# FPGA_DDR3_IO.net
KiCad netlist of a schematic drawn in Altium Designer
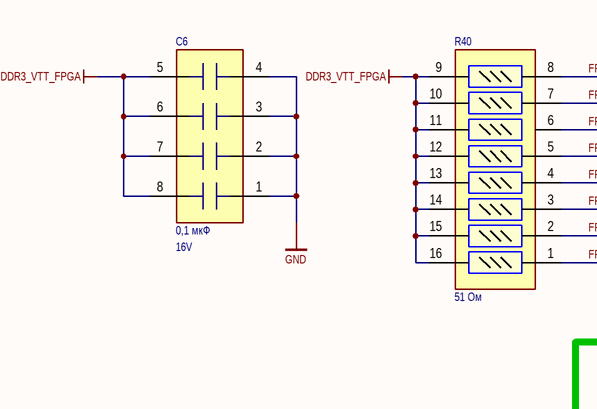
[diagram p0: FPGA_DDR3&IO.SchDoc, top left]
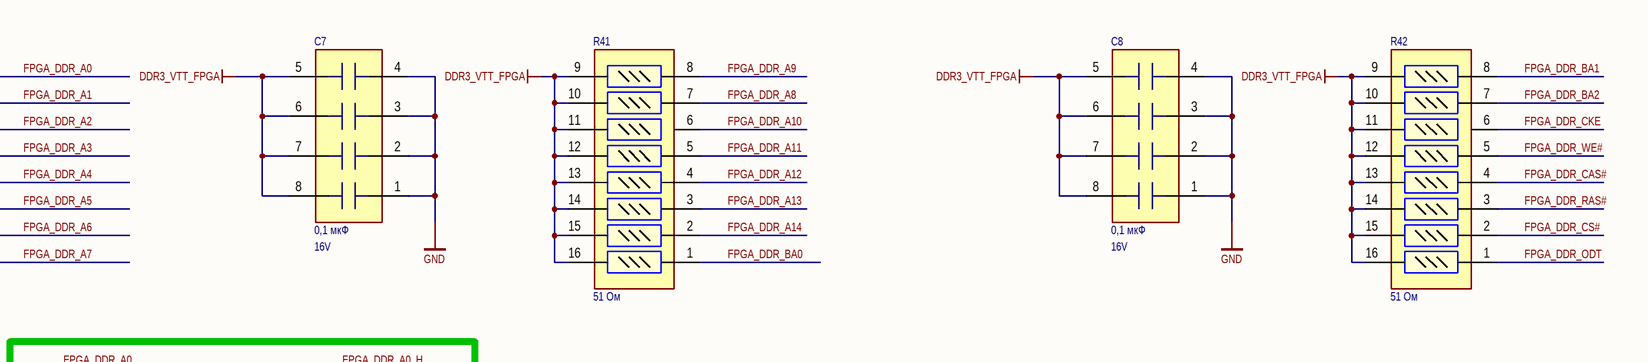
[diagram p1: FPGA_DDR3&IO.SchDoc, top right]
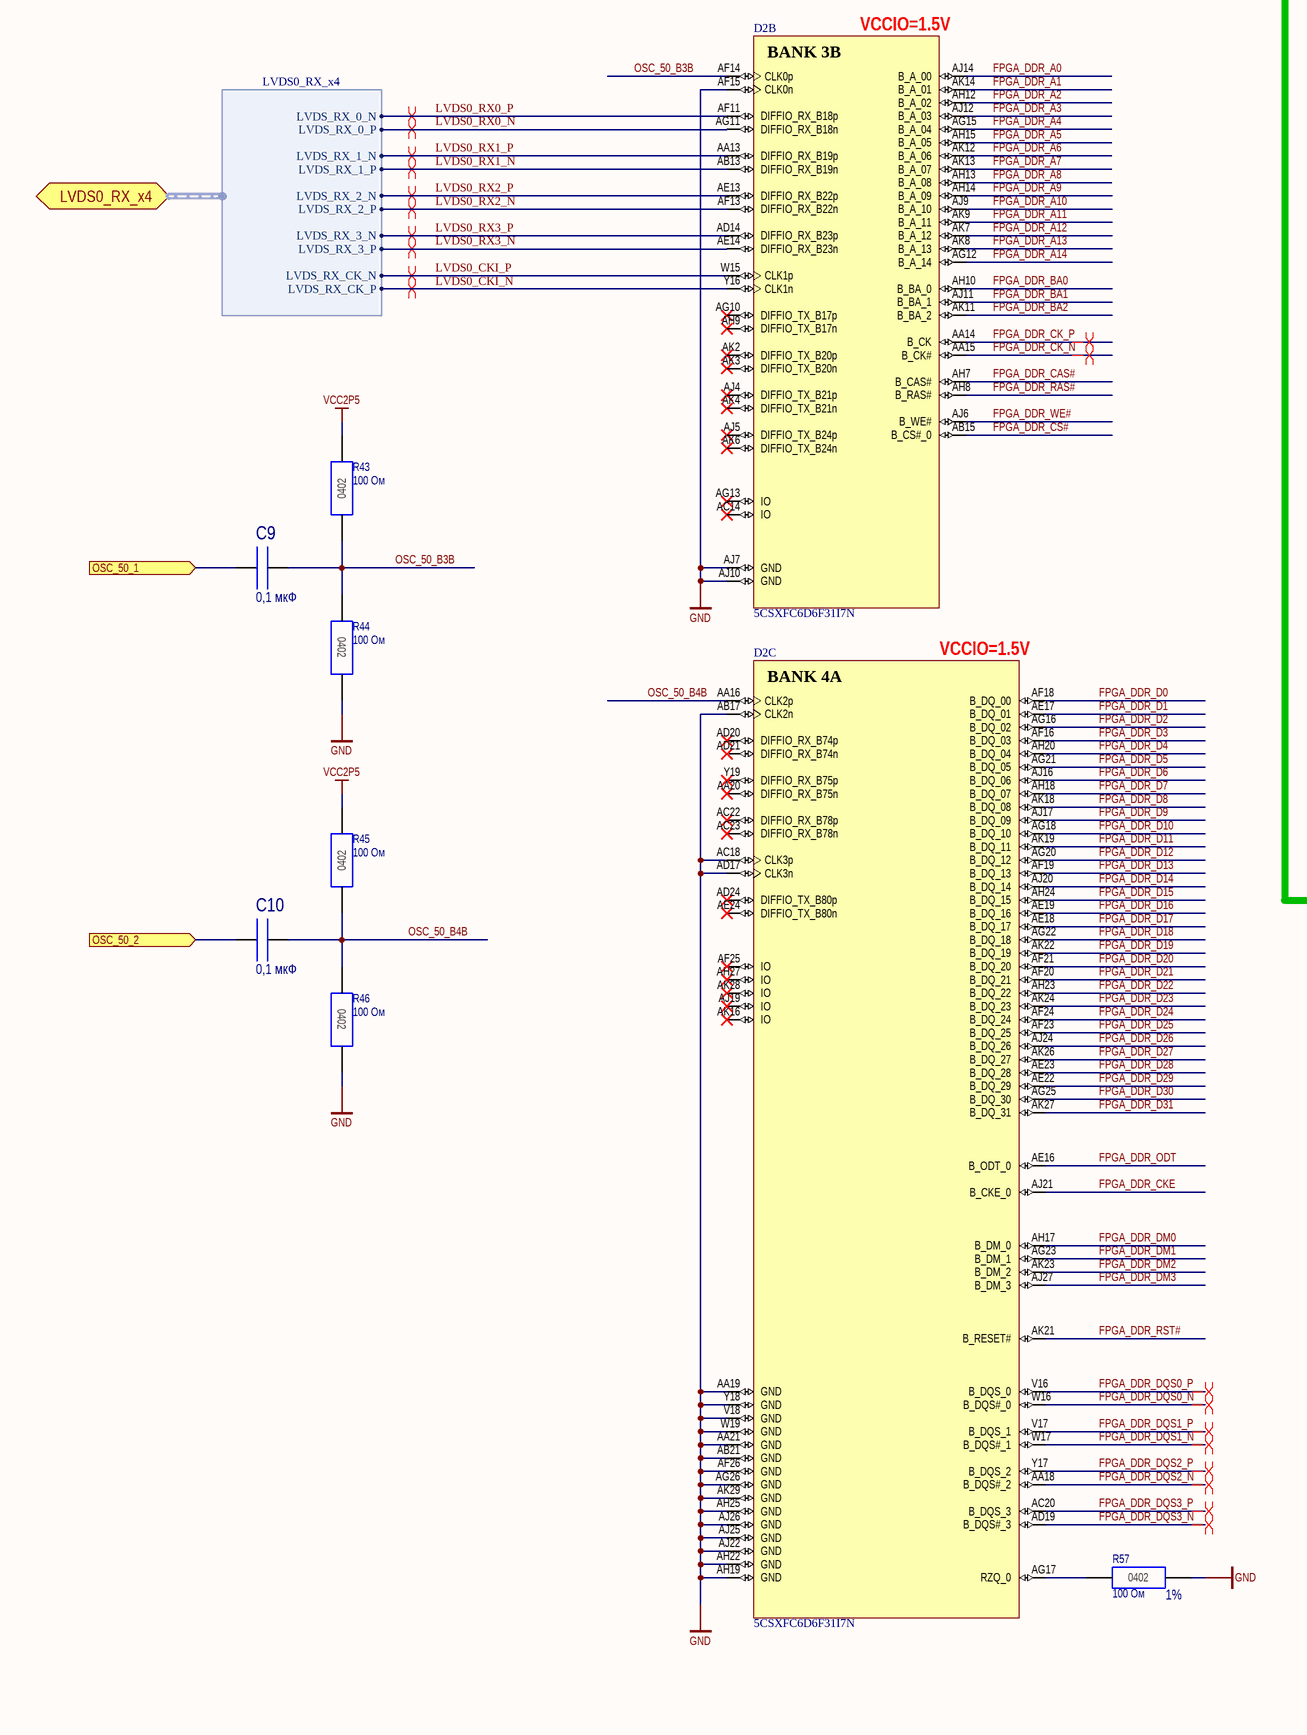
[diagram p2: FPGA_DDR3&IO.SchDoc, bottom left]
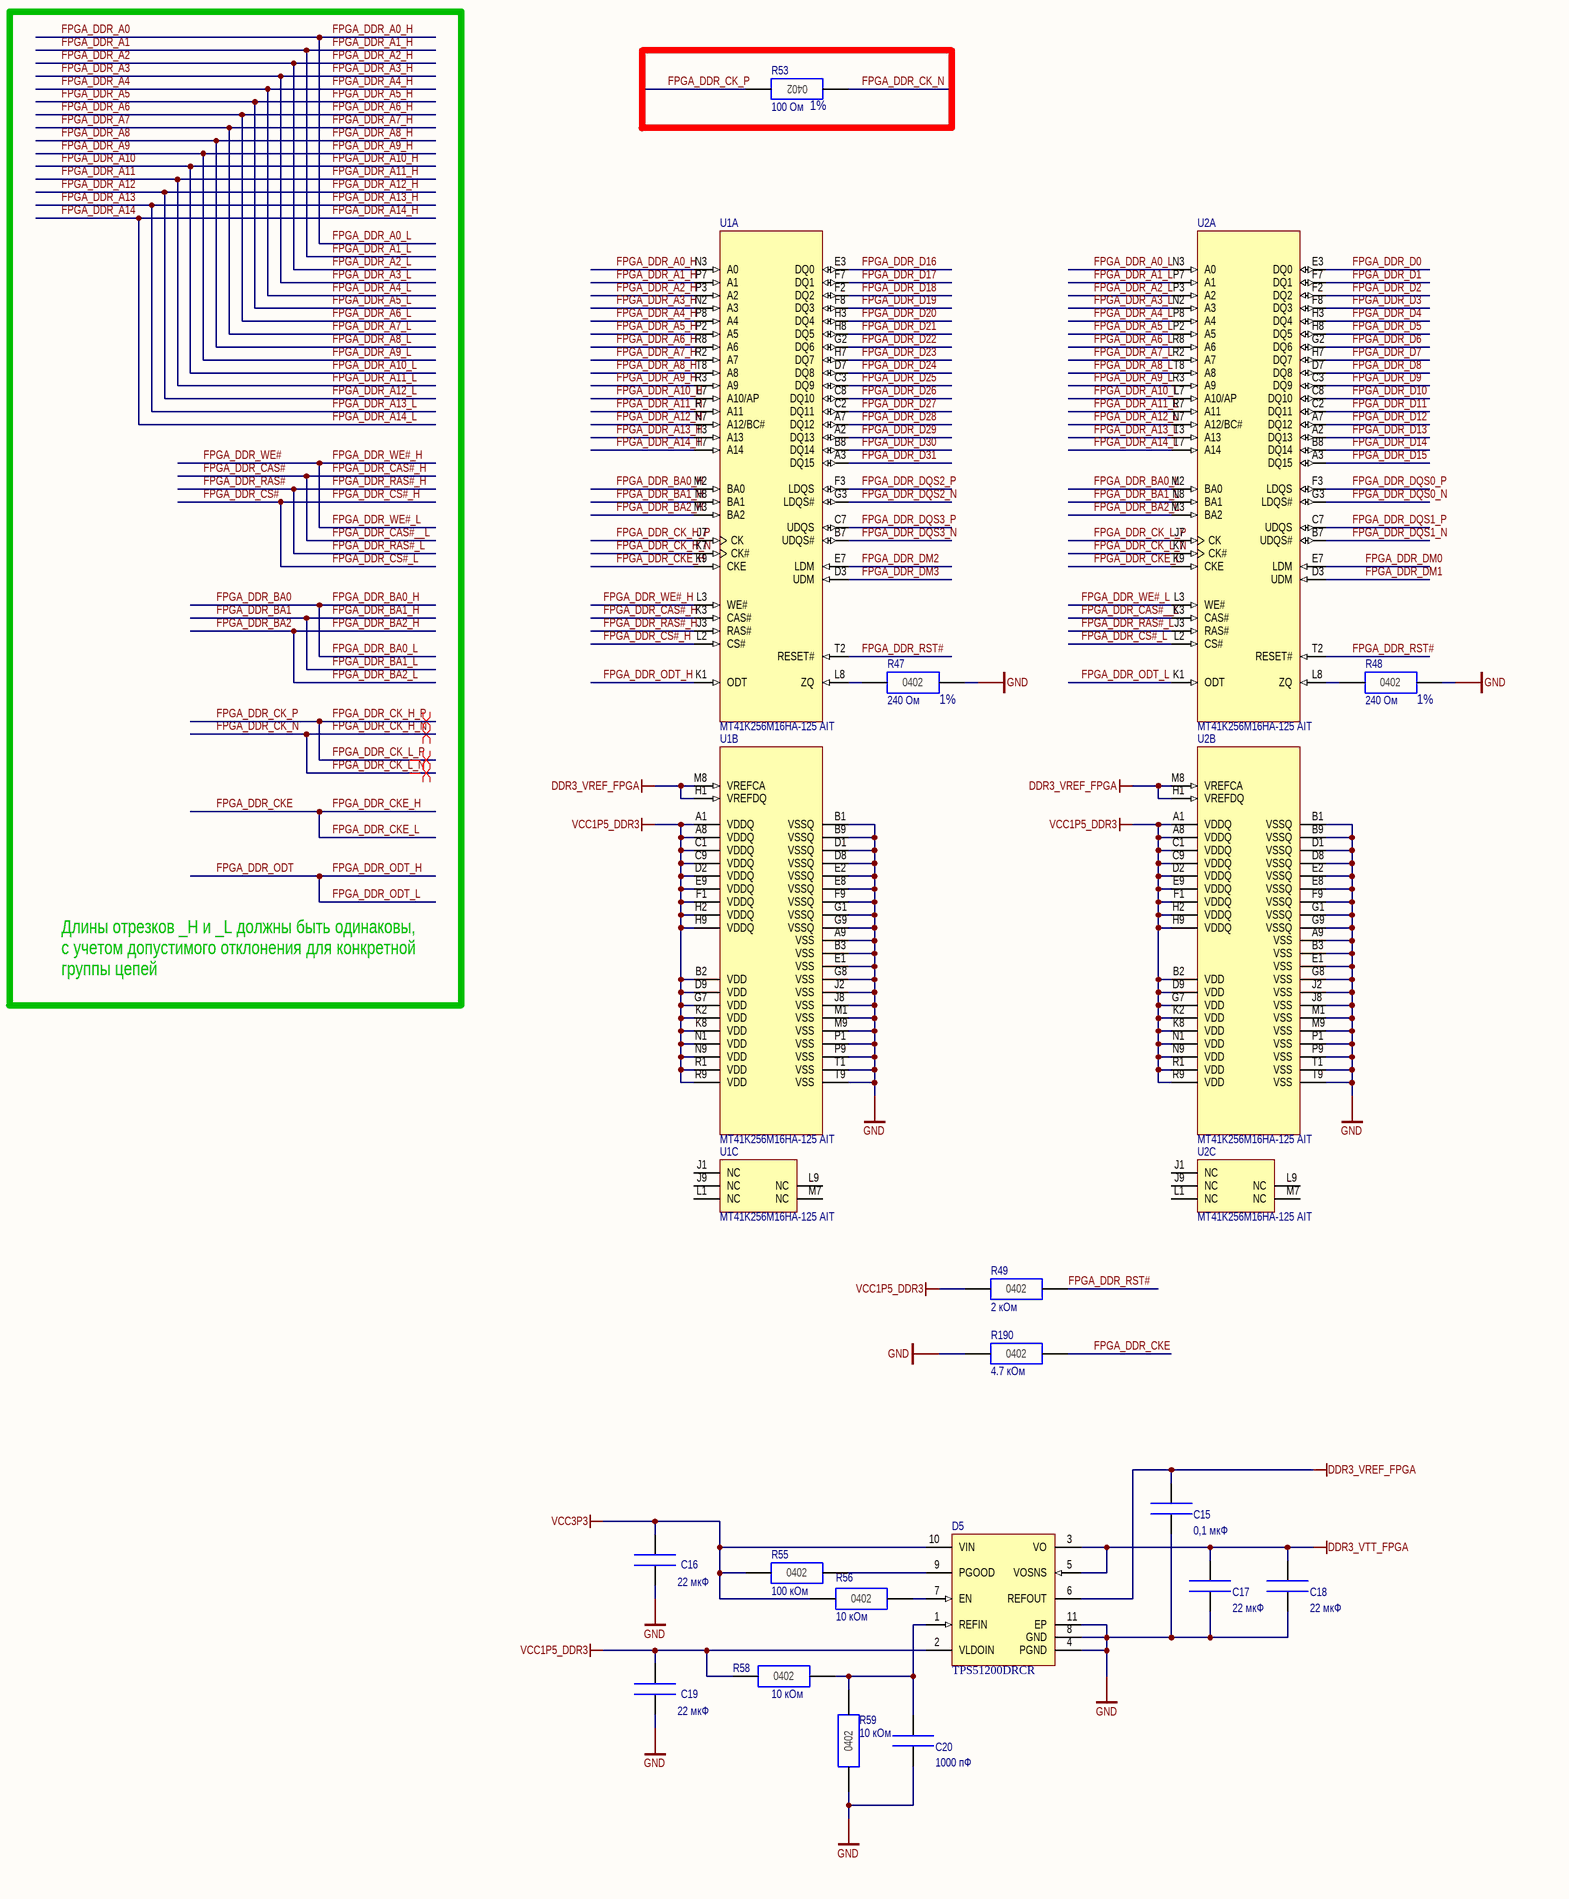
[diagram p3: FPGA_DDR3&IO.SchDoc, bottom right]

(export (version "E")
  (design (tool "Eeschema 10.0.6"))
  (components
    (comp (ref "C6")
      (value "0,1 мкФ")
      (footprint "CAF-80P319X159-8N")
      (description "Чип конденсатор керамический")
      (fields (field (name "V") "16V") (field (name "Comment") "W3A4YC104KAT2A"))
      (libsource (lib "SD_IC") (part "W3A4YC104KAT2A"))
    )
    (comp (ref "C7")
      (value "0,1 мкФ")
      (footprint "CAF-80P319X159-8N")
      (description "Чип конденсатор керамический")
      (fields (field (name "V") "16V") (field (name "Comment") "W3A4YC104KAT2A"))
      (libsource (lib "SD_IC") (part "W3A4YC104KAT2A"))
    )
    (comp (ref "C8")
      (value "0,1 мкФ")
      (footprint "CAF-80P319X159-8N")
      (description "Чип конденсатор керамический")
      (fields (field (name "V") "16V") (field (name "Comment") "W3A4YC104KAT2A"))
      (libsource (lib "SD_IC") (part "W3A4YC104KAT2A"))
    )
    (comp (ref "C9")
      (value "0,1 мкФ")
      (footprint "CC0402(1005)")
      (description "Чип конденсатор керамический")
      (fields (field (name "Comment") "CC0402-X7R-0,1 мкФ-20%-10В"))
      (libsource (lib "Чип конденсаторы") (part "CC0402-X7R-#-20%-10В"))
    )
    (comp (ref "C10")
      (value "0,1 мкФ")
      (footprint "CC0402(1005)")
      (description "Чип конденсатор керамический")
      (fields (field (name "Comment") "CC0402-X7R-0,1 мкФ-20%-10В"))
      (libsource (lib "Чип конденсаторы") (part "CC0402-X7R-#-20%-10В"))
    )
    (comp (ref "C15")
      (value "0,1 мкФ")
      (footprint "CC0402(1005)")
      (description "Чип конденсатор керамический")
      (fields (field (name "Comment") "CC0402-X7R-0,1 мкФ-20%-10В"))
      (libsource (lib "Чип конденсаторы") (part "CC0402-X7R-#-20%-10В"))
    )
    (comp (ref "C16")
      (value "22 мкФ")
      (footprint "CC0402(1005)")
      (description "Чип конденсатор керамический")
      (fields (field (name "Comment") "CC0402-X5R-22 мкФ-20%-6.3В"))
      (libsource (lib "Чип конденсаторы") (part "CC0402-X7R-#-20%-10В"))
    )
    (comp (ref "C17")
      (value "22 мкФ")
      (footprint "CC0402(1005)")
      (description "Чип конденсатор керамический")
      (fields (field (name "Comment") "CC0402-X5R-22 мкФ-20%-6.3В"))
      (libsource (lib "Чип конденсаторы") (part "CC0402-X7R-#-20%-10В"))
    )
    (comp (ref "C18")
      (value "22 мкФ")
      (footprint "CC0402(1005)")
      (description "Чип конденсатор керамический")
      (fields (field (name "Comment") "CC0402-X5R-22 мкФ-20%-6.3В"))
      (libsource (lib "Чип конденсаторы") (part "CC0402-X7R-#-20%-10В"))
    )
    (comp (ref "C19")
      (value "22 мкФ")
      (footprint "CC0402(1005)")
      (description "Чип конденсатор керамический")
      (fields (field (name "Comment") "CC0402-X5R-22 мкФ-20%-6.3В"))
      (libsource (lib "Чип конденсаторы") (part "CC0402-X7R-#-20%-10В"))
    )
    (comp (ref "C20")
      (value "1000 пФ")
      (footprint "CC0402(1005)")
      (description "Чип конденсатор керамический")
      (fields (field (name "Comment") "CC0402-NP01000 пФ-1%-50В"))
      (libsource (lib "Чип конденсаторы") (part "CC0402-X7R-#-20%-10В"))
    )
    (comp (ref "D2")
      (value "5CSXFC6D6F31I7N")
      (footprint "ALTR-FBGA896_A-200")
      (fields (field (name "MANUFACTURER") "Altera"))
      (libsource (lib "Altera Cyclone V_sd") (part "5CSXFC6D6F31I7N"))
    )
    (comp (ref "D5")
      (value "TPS51200DRCR")
      (footprint "TI-DRC10-2400X1650TP_V")
      (fields (field (name "MANUFACTURER") "Texas Instruments"))
      (libsource (lib "SD_IC") (part "TPS51200DRCR"))
    )
    (comp (ref "R40")
      (value "51 Ом")
      (footprint "CAT16-J8")
      (description "Набор чип резисторов")
      (fields (field (name "Comment") "YC248-JR-07-51 Ом"))
      (libsource (lib "SD_IC") (part "YC248-JR-07-#"))
    )
    (comp (ref "R41")
      (value "51 Ом")
      (footprint "CAT16-J8")
      (description "Набор чип резисторов")
      (fields (field (name "Comment") "YC248-JR-07-51 Ом"))
      (libsource (lib "SD_IC") (part "YC248-JR-07-#"))
    )
    (comp (ref "R42")
      (value "51 Ом")
      (footprint "CAT16-J8")
      (description "Набор чип резисторов")
      (fields (field (name "Comment") "YC248-JR-07-51 Ом"))
      (libsource (lib "SD_IC") (part "YC248-JR-07-#"))
    )
    (comp (ref "R43")
      (value "100 Ом")
      (footprint "CR0402(1005)")
      (description "Чип резистор")
      (fields (field (name "TOLERANCE") "5%") (field (name "Comment") "CR0402-100 Ом-±5%"))
      (libsource (lib "") (part "CR0402-#-±5%_3"))
    )
    (comp (ref "R44")
      (value "100 Ом")
      (footprint "CR0402(1005)")
      (description "Чип резистор")
      (fields (field (name "TOLERANCE") "5%") (field (name "Comment") "CR0402-100 Ом-±5%"))
      (libsource (lib "") (part "CR0402-#-±5%_1"))
    )
    (comp (ref "R45")
      (value "100 Ом")
      (footprint "CR0402(1005)")
      (description "Чип резистор")
      (fields (field (name "TOLERANCE") "5%") (field (name "Comment") "CR0402-100 Ом-±5%"))
      (libsource (lib "") (part "CR0402-#-±5%_3"))
    )
    (comp (ref "R46")
      (value "100 Ом")
      (footprint "CR0402(1005)")
      (description "Чип резистор")
      (fields (field (name "TOLERANCE") "5%") (field (name "Comment") "CR0402-100 Ом-±5%"))
      (libsource (lib "") (part "CR0402-#-±5%_1"))
    )
    (comp (ref "R47")
      (value "240 Ом")
      (footprint "CR0402(1005)")
      (description "Чип резистор")
      (fields (field (name "TOLERANCE") "1%") (field (name "Comment") "CR0402-240 Ом-±TOLERANCE"))
      (libsource (lib "Резисторы") (part "CR0402-#-±5%"))
    )
    (comp (ref "R48")
      (value "240 Ом")
      (footprint "CR0402(1005)")
      (description "Чип резистор")
      (fields (field (name "TOLERANCE") "1%") (field (name "Comment") "CR0402-240 Ом-±TOLERANCE"))
      (libsource (lib "Резисторы") (part "CR0402-#-±5%"))
    )
    (comp (ref "R49")
      (value "2 кОм")
      (footprint "CR0402(1005)")
      (description "Чип резистор")
      (fields (field (name "TOLERANCE") "5%") (field (name "Comment") "CR0402-2 кОм-±5%"))
      (libsource (lib "Резисторы") (part "CR0402-#-±5%"))
    )
    (comp (ref "R53")
      (value "100 Ом")
      (footprint "CR0402(1005)")
      (description "Чип резистор")
      (fields (field (name "TOLERANCE") "1%") (field (name "Comment") "CR0402-100 Ом-±TOLERANCE"))
      (libsource (lib "") (part "CR0402-#-±5%_2"))
    )
    (comp (ref "R55")
      (value "100 кОм")
      (footprint "CR0402(1005)")
      (description "Чип резистор")
      (fields (field (name "TOLERANCE") "5%") (field (name "Comment") "CR0402-100 кОм-±5%"))
      (libsource (lib "Резисторы") (part "CR0402-#-±5%"))
    )
    (comp (ref "R56")
      (value "10 кОм")
      (footprint "CR0402(1005)")
      (description "Чип резистор")
      (fields (field (name "TOLERANCE") "5%") (field (name "Comment") "CR0402-10 кОм-±5%"))
      (libsource (lib "Резисторы") (part "CR0402-#-±5%"))
    )
    (comp (ref "R57")
      (value "100 Ом")
      (footprint "CR0402(1005)")
      (description "Чип резистор")
      (fields (field (name "TOLERANCE") "1%") (field (name "Comment") "CR0402-100 Ом-±TOLERANCE"))
      (libsource (lib "Резисторы") (part "CR0402-#-±5%"))
    )
    (comp (ref "R58")
      (value "10 кОм")
      (footprint "CR0402(1005)")
      (description "Чип резистор")
      (fields (field (name "TOLERANCE") "5%") (field (name "Comment") "CR0402-10 кОм-±5%"))
      (libsource (lib "Резисторы") (part "CR0402-#-±5%"))
    )
    (comp (ref "R59")
      (value "10 кОм")
      (footprint "CR0402(1005)")
      (description "Чип резистор")
      (fields (field (name "TOLERANCE") "5%") (field (name "Comment") "CR0402-10 кОм-±5%"))
      (libsource (lib "") (part "CR0402-#-±5%_3"))
    )
    (comp (ref "R190")
      (value "4.7 кОм")
      (footprint "CR0402(1005)")
      (description "Чип резистор")
      (fields (field (name "TOLERANCE") "5%") (field (name "Comment") "CR0402-4.7 кОм-±5%"))
      (libsource (lib "Резисторы") (part "CR0402-#-±5%"))
    )
    (comp (ref "U1")
      (value "MT41K256M16HA-125 AIT")
      (footprint "MICT-HA-96")
      (description "4Gb DDR3-1600 SDRAM, 256Mb x 16, 1.25ns, 1.35V, -40 to 95 degC, 96-Ball FBGA, Pb-Free")
      (fields (field (name "VOLTAGE") "1.35V ") (field (name "MANUFACTURER") "Micron"))
      (libsource (lib "SD_IC") (part "MT41K256M16HA-125 AIT"))
    )
    (comp (ref "U2")
      (value "MT41K256M16HA-125 AIT")
      (footprint "MICT-HA-96")
      (description "4Gb DDR3-1600 SDRAM, 256Mb x 16, 1.25ns, 1.35V, -40 to 95 degC, 96-Ball FBGA, Pb-Free")
      (fields (field (name "VOLTAGE") "1.35V ") (field (name "MANUFACTURER") "Micron"))
      (libsource (lib "SD_IC") (part "MT41K256M16HA-125 AIT"))
    )
  )
  (nets
    (net (code "2") (name "/FPGA_DDR_A0") (class "Default")
      (node (ref "D2") (pin "AJ14") (pinfunction "B_A_00_AJ14") (pintype "bidirectional"))
      (node (ref "R40") (pin "8") (pintype "passive"))
      (node (ref "U1") (pin "N3") (pinfunction "A0_N3") (pintype "input"))
      (node (ref "U2") (pin "N3") (pinfunction "A0_N3") (pintype "input"))
    )
    (net (code "3") (name "/FPGA_DDR_A1") (class "Default")
      (node (ref "D2") (pin "AK14") (pinfunction "B_A_01_AK14") (pintype "bidirectional"))
      (node (ref "R40") (pin "7") (pintype "passive"))
      (node (ref "U1") (pin "P7") (pinfunction "A1_P7") (pintype "input"))
      (node (ref "U2") (pin "P7") (pinfunction "A1_P7") (pintype "input"))
    )
    (net (code "4") (name "/FPGA_DDR_A2") (class "Default")
      (node (ref "D2") (pin "AH12") (pinfunction "B_A_02_AH12") (pintype "bidirectional"))
      (node (ref "R40") (pin "6") (pintype "passive"))
      (node (ref "U1") (pin "P3") (pinfunction "A2_P3") (pintype "input"))
      (node (ref "U2") (pin "P3") (pinfunction "A2_P3") (pintype "input"))
    )
    (net (code "5") (name "/FPGA_DDR_A3") (class "Default")
      (node (ref "D2") (pin "AJ12") (pinfunction "B_A_03_AJ12") (pintype "bidirectional"))
      (node (ref "R40") (pin "5") (pintype "passive"))
      (node (ref "U1") (pin "N2") (pinfunction "A3_N2") (pintype "input"))
      (node (ref "U2") (pin "N2") (pinfunction "A3_N2") (pintype "input"))
    )
    (net (code "6") (name "/FPGA_DDR_A4") (class "Default")
      (node (ref "D2") (pin "AG15") (pinfunction "B_A_04_AG15") (pintype "bidirectional"))
      (node (ref "R40") (pin "4") (pintype "passive"))
      (node (ref "U1") (pin "P8") (pinfunction "A4_P8") (pintype "input"))
      (node (ref "U2") (pin "P8") (pinfunction "A4_P8") (pintype "input"))
    )
    (net (code "7") (name "/FPGA_DDR_A5") (class "Default")
      (node (ref "D2") (pin "AH15") (pinfunction "B_A_05_AH15") (pintype "bidirectional"))
      (node (ref "R40") (pin "3") (pintype "passive"))
      (node (ref "U1") (pin "P2") (pinfunction "A5_P2") (pintype "input"))
      (node (ref "U2") (pin "P2") (pinfunction "A5_P2") (pintype "input"))
    )
    (net (code "8") (name "/FPGA_DDR_A6") (class "Default")
      (node (ref "D2") (pin "AK12") (pinfunction "B_A_06_AK12") (pintype "bidirectional"))
      (node (ref "R40") (pin "2") (pintype "passive"))
      (node (ref "U1") (pin "R8") (pinfunction "A6_R8") (pintype "input"))
      (node (ref "U2") (pin "R8") (pinfunction "A6_R8") (pintype "input"))
    )
    (net (code "9") (name "/FPGA_DDR_A7") (class "Default")
      (node (ref "D2") (pin "AK13") (pinfunction "B_A_07_AK13") (pintype "bidirectional"))
      (node (ref "R40") (pin "1") (pintype "passive"))
      (node (ref "U1") (pin "R2") (pinfunction "A7_R2") (pintype "input"))
      (node (ref "U2") (pin "R2") (pinfunction "A7_R2") (pintype "input"))
    )
    (net (code "10") (name "/FPGA_DDR_A8") (class "Default")
      (node (ref "D2") (pin "AH13") (pinfunction "B_A_08_AH13") (pintype "bidirectional"))
      (node (ref "R41") (pin "7") (pintype "passive"))
      (node (ref "U1") (pin "T8") (pinfunction "A8_T8") (pintype "input"))
      (node (ref "U2") (pin "T8") (pinfunction "A8_T8") (pintype "input"))
    )
    (net (code "11") (name "/FPGA_DDR_A9") (class "Default")
      (node (ref "D2") (pin "AH14") (pinfunction "B_A_09_AH14") (pintype "bidirectional"))
      (node (ref "R41") (pin "8") (pintype "passive"))
      (node (ref "U1") (pin "R3") (pinfunction "A9_R3") (pintype "input"))
      (node (ref "U2") (pin "R3") (pinfunction "A9_R3") (pintype "input"))
    )
    (net (code "12") (name "/FPGA_DDR_A10") (class "Default")
      (node (ref "D2") (pin "AJ9") (pinfunction "B_A_10_AJ9") (pintype "bidirectional"))
      (node (ref "R41") (pin "6") (pintype "passive"))
      (node (ref "U1") (pin "L7") (pinfunction "A10/AP_L7") (pintype "input"))
      (node (ref "U2") (pin "L7") (pinfunction "A10/AP_L7") (pintype "input"))
    )
    (net (code "13") (name "/FPGA_DDR_A11") (class "Default")
      (node (ref "D2") (pin "AK9") (pinfunction "B_A_11_AK9") (pintype "bidirectional"))
      (node (ref "R41") (pin "5") (pintype "passive"))
      (node (ref "U1") (pin "R7") (pinfunction "A11_R7") (pintype "input"))
      (node (ref "U2") (pin "R7") (pinfunction "A11_R7") (pintype "input"))
    )
    (net (code "14") (name "/FPGA_DDR_A12") (class "Default")
      (node (ref "D2") (pin "AK7") (pinfunction "B_A_12_AK7") (pintype "bidirectional"))
      (node (ref "R41") (pin "4") (pintype "passive"))
      (node (ref "U1") (pin "N7") (pinfunction "A12/BC#_N7") (pintype "input"))
      (node (ref "U2") (pin "N7") (pinfunction "A12/BC#_N7") (pintype "input"))
    )
    (net (code "15") (name "/FPGA_DDR_A13") (class "Default")
      (node (ref "D2") (pin "AK8") (pinfunction "B_A_13_AK8") (pintype "bidirectional"))
      (node (ref "R41") (pin "3") (pintype "passive"))
      (node (ref "U1") (pin "T3") (pinfunction "A13_T3") (pintype "input"))
      (node (ref "U2") (pin "T3") (pinfunction "A13_T3") (pintype "input"))
    )
    (net (code "16") (name "/FPGA_DDR_A14") (class "Default")
      (node (ref "D2") (pin "AG12") (pinfunction "B_A_14_AG12") (pintype "bidirectional"))
      (node (ref "R41") (pin "2") (pintype "passive"))
      (node (ref "U1") (pin "T7") (pinfunction "A14_T7") (pintype "input"))
      (node (ref "U2") (pin "T7") (pinfunction "A14_T7") (pintype "input"))
    )
    (net (code "17") (name "/FPGA_DDR_BA0") (class "Default")
      (node (ref "D2") (pin "AH10") (pinfunction "B_BA_0_AH10") (pintype "bidirectional"))
      (node (ref "R41") (pin "1") (pintype "passive"))
      (node (ref "U1") (pin "M2") (pinfunction "BA0_M2") (pintype "input"))
      (node (ref "U2") (pin "M2") (pinfunction "BA0_M2") (pintype "input"))
    )
    (net (code "18") (name "/FPGA_DDR_BA1") (class "Default")
      (node (ref "D2") (pin "AJ11") (pinfunction "B_BA_1_AJ11") (pintype "bidirectional"))
      (node (ref "R42") (pin "8") (pintype "passive"))
      (node (ref "U1") (pin "N8") (pinfunction "BA1_N8") (pintype "input"))
      (node (ref "U2") (pin "N8") (pinfunction "BA1_N8") (pintype "input"))
    )
    (net (code "19") (name "/FPGA_DDR_BA2") (class "Default")
      (node (ref "D2") (pin "AK11") (pinfunction "B_BA_2_AK11") (pintype "bidirectional"))
      (node (ref "R42") (pin "7") (pintype "passive"))
      (node (ref "U1") (pin "M3") (pinfunction "BA2_M3") (pintype "input"))
      (node (ref "U2") (pin "M3") (pinfunction "BA2_M3") (pintype "input"))
    )
    (net (code "20") (name "/FPGA_DDR_CAS#") (class "Default")
      (node (ref "D2") (pin "AH7") (pinfunction "B_CAS#_AH7") (pintype "bidirectional"))
      (node (ref "R42") (pin "4") (pintype "passive"))
      (node (ref "U1") (pin "K3") (pinfunction "CAS#_K3") (pintype "input"))
      (node (ref "U2") (pin "K3") (pinfunction "CAS#_K3") (pintype "input"))
    )
    (net (code "21") (name "/FPGA_DDR_CKE") (class "Default")
      (node (ref "D2") (pin "AJ21") (pinfunction "B_CKE_0_AJ21") (pintype "bidirectional"))
      (node (ref "R190") (pin "2") (pinfunction "-_2") (pintype "passive"))
      (node (ref "R42") (pin "6") (pintype "passive"))
      (node (ref "U1") (pin "K9") (pinfunction "CKE_K9") (pintype "input"))
      (node (ref "U2") (pin "K9") (pinfunction "CKE_K9") (pintype "input"))
    )
    (net (code "22") (name "/FPGA_DDR_CK_H_N") (class "Default")
      (node (ref "D2") (pin "AA15") (pinfunction "B_CK#_AA15") (pintype "bidirectional"))
      (node (ref "R53") (pin "1") (pinfunction "+_1") (pintype "passive"))
      (node (ref "U1") (pin "K7") (pinfunction "CK#_K7") (pintype "input"))
      (node (ref "U2") (pin "K7") (pinfunction "CK#_K7") (pintype "input"))
    )
    (net (code "23") (name "/FPGA_DDR_CK_H_P") (class "Default")
      (node (ref "D2") (pin "AA14") (pinfunction "B_CK_AA14") (pintype "bidirectional"))
      (node (ref "R53") (pin "2") (pinfunction "-_2") (pintype "passive"))
      (node (ref "U1") (pin "J7") (pinfunction "CK_J7") (pintype "input"))
      (node (ref "U2") (pin "J7") (pinfunction "CK_J7") (pintype "input"))
    )
    (net (code "24") (name "/FPGA_DDR_CS#") (class "Default")
      (node (ref "D2") (pin "AB15") (pinfunction "B_CS#_0_AB15") (pintype "bidirectional"))
      (node (ref "R42") (pin "2") (pintype "passive"))
      (node (ref "U1") (pin "L2") (pinfunction "CS#_L2") (pintype "input"))
      (node (ref "U2") (pin "L2") (pinfunction "CS#_L2") (pintype "input"))
    )
    (net (code "25") (name "/FPGA_DDR_D0") (class "Default")
      (node (ref "D2") (pin "AF18") (pinfunction "B_DQ_00_AF18") (pintype "bidirectional"))
      (node (ref "U2") (pin "E3") (pinfunction "DQ0_E3") (pintype "bidirectional"))
    )
    (net (code "26") (name "/FPGA_DDR_D1") (class "Default")
      (node (ref "D2") (pin "AE17") (pinfunction "B_DQ_01_AE17") (pintype "bidirectional"))
      (node (ref "U2") (pin "F7") (pinfunction "DQ1_F7") (pintype "bidirectional"))
    )
    (net (code "27") (name "/FPGA_DDR_D2") (class "Default")
      (node (ref "D2") (pin "AG16") (pinfunction "B_DQ_02_AG16") (pintype "bidirectional"))
      (node (ref "U2") (pin "F2") (pinfunction "DQ2_F2") (pintype "bidirectional"))
    )
    (net (code "28") (name "/FPGA_DDR_D3") (class "Default")
      (node (ref "D2") (pin "AF16") (pinfunction "B_DQ_03_AF16") (pintype "bidirectional"))
      (node (ref "U2") (pin "F8") (pinfunction "DQ3_F8") (pintype "bidirectional"))
    )
    (net (code "29") (name "/FPGA_DDR_D4") (class "Default")
      (node (ref "D2") (pin "AH20") (pinfunction "B_DQ_04_AH20") (pintype "bidirectional"))
      (node (ref "U2") (pin "H3") (pinfunction "DQ4_H3") (pintype "bidirectional"))
    )
    (net (code "30") (name "/FPGA_DDR_D5") (class "Default")
      (node (ref "D2") (pin "AG21") (pinfunction "B_DQ_05_AG21") (pintype "bidirectional"))
      (node (ref "U2") (pin "H8") (pinfunction "DQ5_H8") (pintype "bidirectional"))
    )
    (net (code "31") (name "/FPGA_DDR_D6") (class "Default")
      (node (ref "D2") (pin "AJ16") (pinfunction "B_DQ_06_AJ16") (pintype "bidirectional"))
      (node (ref "U2") (pin "G2") (pinfunction "DQ6_G2") (pintype "bidirectional"))
    )
    (net (code "32") (name "/FPGA_DDR_D7") (class "Default")
      (node (ref "D2") (pin "AH18") (pinfunction "B_DQ_07_AH18") (pintype "bidirectional"))
      (node (ref "U2") (pin "H7") (pinfunction "DQ7_H7") (pintype "bidirectional"))
    )
    (net (code "33") (name "/FPGA_DDR_D8") (class "Default")
      (node (ref "D2") (pin "AK18") (pinfunction "B_DQ_08_AK18") (pintype "bidirectional"))
      (node (ref "U2") (pin "D7") (pinfunction "DQ8_D7") (pintype "bidirectional"))
    )
    (net (code "34") (name "/FPGA_DDR_D9") (class "Default")
      (node (ref "D2") (pin "AJ17") (pinfunction "B_DQ_09_AJ17") (pintype "bidirectional"))
      (node (ref "U2") (pin "C3") (pinfunction "DQ9_C3") (pintype "bidirectional"))
    )
    (net (code "35") (name "/FPGA_DDR_D10") (class "Default")
      (node (ref "D2") (pin "AG18") (pinfunction "B_DQ_10_AG18") (pintype "bidirectional"))
      (node (ref "U2") (pin "C8") (pinfunction "DQ10_C8") (pintype "bidirectional"))
    )
    (net (code "36") (name "/FPGA_DDR_D11") (class "Default")
      (node (ref "D2") (pin "AK19") (pinfunction "B_DQ_11_AK19") (pintype "bidirectional"))
      (node (ref "U2") (pin "C2") (pinfunction "DQ11_C2") (pintype "bidirectional"))
    )
    (net (code "37") (name "/FPGA_DDR_D12") (class "Default")
      (node (ref "D2") (pin "AG20") (pinfunction "B_DQ_12_AG20") (pintype "bidirectional"))
      (node (ref "U2") (pin "A7") (pinfunction "DQ12_A7") (pintype "bidirectional"))
    )
    (net (code "38") (name "/FPGA_DDR_D13") (class "Default")
      (node (ref "D2") (pin "AF19") (pinfunction "B_DQ_13_AF19") (pintype "bidirectional"))
      (node (ref "U2") (pin "A2") (pinfunction "DQ13_A2") (pintype "bidirectional"))
    )
    (net (code "39") (name "/FPGA_DDR_D14") (class "Default")
      (node (ref "D2") (pin "AJ20") (pinfunction "B_DQ_14_AJ20") (pintype "bidirectional"))
      (node (ref "U2") (pin "B8") (pinfunction "DQ14_B8") (pintype "bidirectional"))
    )
    (net (code "40") (name "/FPGA_DDR_D15") (class "Default")
      (node (ref "D2") (pin "AH24") (pinfunction "B_DQ_15_AH24") (pintype "bidirectional"))
      (node (ref "U2") (pin "A3") (pinfunction "DQ15_A3") (pintype "bidirectional"))
    )
    (net (code "41") (name "/FPGA_DDR_D16") (class "Default")
      (node (ref "D2") (pin "AE19") (pinfunction "B_DQ_16_AE19") (pintype "bidirectional"))
      (node (ref "U1") (pin "E3") (pinfunction "DQ0_E3") (pintype "bidirectional"))
    )
    (net (code "42") (name "/FPGA_DDR_D17") (class "Default")
      (node (ref "D2") (pin "AE18") (pinfunction "B_DQ_17_AE18") (pintype "bidirectional"))
      (node (ref "U1") (pin "F7") (pinfunction "DQ1_F7") (pintype "bidirectional"))
    )
    (net (code "43") (name "/FPGA_DDR_D18") (class "Default")
      (node (ref "D2") (pin "AG22") (pinfunction "B_DQ_18_AG22") (pintype "bidirectional"))
      (node (ref "U1") (pin "F2") (pinfunction "DQ2_F2") (pintype "bidirectional"))
    )
    (net (code "44") (name "/FPGA_DDR_D19") (class "Default")
      (node (ref "D2") (pin "AK22") (pinfunction "B_DQ_19_AK22") (pintype "bidirectional"))
      (node (ref "U1") (pin "F8") (pinfunction "DQ3_F8") (pintype "bidirectional"))
    )
    (net (code "45") (name "/FPGA_DDR_D20") (class "Default")
      (node (ref "D2") (pin "AF21") (pinfunction "B_DQ_20_AF21") (pintype "bidirectional"))
      (node (ref "U1") (pin "H3") (pinfunction "DQ4_H3") (pintype "bidirectional"))
    )
    (net (code "46") (name "/FPGA_DDR_D21") (class "Default")
      (node (ref "D2") (pin "AF20") (pinfunction "B_DQ_21_AF20") (pintype "bidirectional"))
      (node (ref "U1") (pin "H8") (pinfunction "DQ5_H8") (pintype "bidirectional"))
    )
    (net (code "47") (name "/FPGA_DDR_D22") (class "Default")
      (node (ref "D2") (pin "AH23") (pinfunction "B_DQ_22_AH23") (pintype "bidirectional"))
      (node (ref "U1") (pin "G2") (pinfunction "DQ6_G2") (pintype "bidirectional"))
    )
    (net (code "48") (name "/FPGA_DDR_D23") (class "Default")
      (node (ref "D2") (pin "AK24") (pinfunction "B_DQ_23_AK24") (pintype "bidirectional"))
      (node (ref "U1") (pin "H7") (pinfunction "DQ7_H7") (pintype "bidirectional"))
    )
    (net (code "49") (name "/FPGA_DDR_D24") (class "Default")
      (node (ref "D2") (pin "AF24") (pinfunction "B_DQ_24_AF24") (pintype "bidirectional"))
      (node (ref "U1") (pin "D7") (pinfunction "DQ8_D7") (pintype "bidirectional"))
    )
    (net (code "50") (name "/FPGA_DDR_D25") (class "Default")
      (node (ref "D2") (pin "AF23") (pinfunction "B_DQ_25_AF23") (pintype "bidirectional"))
      (node (ref "U1") (pin "C3") (pinfunction "DQ9_C3") (pintype "bidirectional"))
    )
    (net (code "51") (name "/FPGA_DDR_D26") (class "Default")
      (node (ref "D2") (pin "AJ24") (pinfunction "B_DQ_26_AJ24") (pintype "bidirectional"))
      (node (ref "U1") (pin "C8") (pinfunction "DQ10_C8") (pintype "bidirectional"))
    )
    (net (code "52") (name "/FPGA_DDR_D27") (class "Default")
      (node (ref "D2") (pin "AK26") (pinfunction "B_DQ_27_AK26") (pintype "bidirectional"))
      (node (ref "U1") (pin "C2") (pinfunction "DQ11_C2") (pintype "bidirectional"))
    )
    (net (code "53") (name "/FPGA_DDR_D28") (class "Default")
      (node (ref "D2") (pin "AE23") (pinfunction "B_DQ_28_AE23") (pintype "bidirectional"))
      (node (ref "U1") (pin "A7") (pinfunction "DQ12_A7") (pintype "bidirectional"))
    )
    (net (code "54") (name "/FPGA_DDR_D29") (class "Default")
      (node (ref "D2") (pin "AE22") (pinfunction "B_DQ_29_AE22") (pintype "bidirectional"))
      (node (ref "U1") (pin "A2") (pinfunction "DQ13_A2") (pintype "bidirectional"))
    )
    (net (code "55") (name "/FPGA_DDR_D30") (class "Default")
      (node (ref "D2") (pin "AG25") (pinfunction "B_DQ_30_AG25") (pintype "bidirectional"))
      (node (ref "U1") (pin "B8") (pinfunction "DQ14_B8") (pintype "bidirectional"))
    )
    (net (code "56") (name "/FPGA_DDR_D31") (class "Default")
      (node (ref "D2") (pin "AK27") (pinfunction "B_DQ_31_AK27") (pintype "bidirectional"))
      (node (ref "U1") (pin "A3") (pinfunction "DQ15_A3") (pintype "bidirectional"))
    )
    (net (code "57") (name "/FPGA_DDR_DM0") (class "Default")
      (node (ref "D2") (pin "AH17") (pinfunction "B_DM_0_AH17") (pintype "bidirectional"))
      (node (ref "U2") (pin "E7") (pinfunction "LDM_E7") (pintype "input"))
    )
    (net (code "58") (name "/FPGA_DDR_DM1") (class "Default")
      (node (ref "D2") (pin "AG23") (pinfunction "B_DM_1_AG23") (pintype "bidirectional"))
      (node (ref "U2") (pin "D3") (pinfunction "UDM_D3") (pintype "input"))
    )
    (net (code "59") (name "/FPGA_DDR_DM2") (class "Default")
      (node (ref "D2") (pin "AK23") (pinfunction "B_DM_2_AK23") (pintype "bidirectional"))
      (node (ref "U1") (pin "E7") (pinfunction "LDM_E7") (pintype "input"))
    )
    (net (code "60") (name "/FPGA_DDR_DM3") (class "Default")
      (node (ref "D2") (pin "AJ27") (pinfunction "B_DM_3_AJ27") (pintype "bidirectional"))
      (node (ref "U1") (pin "D3") (pinfunction "UDM_D3") (pintype "input"))
    )
    (net (code "61") (name "/FPGA_DDR_DQS0_N") (class "Default")
      (node (ref "D2") (pin "W16") (pinfunction "B_DQS#_0_W16") (pintype "bidirectional"))
      (node (ref "U2") (pin "G3") (pinfunction "LDQS#_G3") (pintype "bidirectional"))
    )
    (net (code "62") (name "/FPGA_DDR_DQS0_P") (class "Default")
      (node (ref "D2") (pin "V16") (pinfunction "B_DQS_0_V16") (pintype "bidirectional"))
      (node (ref "U2") (pin "F3") (pinfunction "LDQS_F3") (pintype "bidirectional"))
    )
    (net (code "63") (name "/FPGA_DDR_DQS1_N") (class "Default")
      (node (ref "D2") (pin "W17") (pinfunction "B_DQS#_1_W17") (pintype "bidirectional"))
      (node (ref "U2") (pin "B7") (pinfunction "UDQS#_B7") (pintype "bidirectional"))
    )
    (net (code "64") (name "/FPGA_DDR_DQS1_P") (class "Default")
      (node (ref "D2") (pin "V17") (pinfunction "B_DQS_1_V17") (pintype "bidirectional"))
      (node (ref "U2") (pin "C7") (pinfunction "UDQS_C7") (pintype "bidirectional"))
    )
    (net (code "65") (name "/FPGA_DDR_DQS2_N") (class "Default")
      (node (ref "D2") (pin "AA18") (pinfunction "B_DQS#_2_AA18") (pintype "bidirectional"))
      (node (ref "U1") (pin "G3") (pinfunction "LDQS#_G3") (pintype "bidirectional"))
    )
    (net (code "66") (name "/FPGA_DDR_DQS2_P") (class "Default")
      (node (ref "D2") (pin "Y17") (pinfunction "B_DQS_2_Y17") (pintype "bidirectional"))
      (node (ref "U1") (pin "F3") (pinfunction "LDQS_F3") (pintype "bidirectional"))
    )
    (net (code "67") (name "/FPGA_DDR_DQS3_N") (class "Default")
      (node (ref "D2") (pin "AD19") (pinfunction "B_DQS#_3_AD19") (pintype "bidirectional"))
      (node (ref "U1") (pin "B7") (pinfunction "UDQS#_B7") (pintype "bidirectional"))
    )
    (net (code "68") (name "/FPGA_DDR_DQS3_P") (class "Default")
      (node (ref "D2") (pin "AC20") (pinfunction "B_DQS_3_AC20") (pintype "bidirectional"))
      (node (ref "U1") (pin "C7") (pinfunction "UDQS_C7") (pintype "bidirectional"))
    )
    (net (code "69") (name "/FPGA_DDR_ODT") (class "Default")
      (node (ref "D2") (pin "AE16") (pinfunction "B_ODT_0_AE16") (pintype "bidirectional"))
      (node (ref "R42") (pin "1") (pintype "passive"))
      (node (ref "U1") (pin "K1") (pinfunction "ODT_K1") (pintype "input"))
      (node (ref "U2") (pin "K1") (pinfunction "ODT_K1") (pintype "input"))
    )
    (net (code "70") (name "/FPGA_DDR_RAS#") (class "Default")
      (node (ref "D2") (pin "AH8") (pinfunction "B_RAS#_AH8") (pintype "bidirectional"))
      (node (ref "R42") (pin "3") (pintype "passive"))
      (node (ref "U1") (pin "J3") (pinfunction "RAS#_J3") (pintype "input"))
      (node (ref "U2") (pin "J3") (pinfunction "RAS#_J3") (pintype "input"))
    )
    (net (code "71") (name "/FPGA_DDR_RST#") (class "Default")
      (node (ref "D2") (pin "AK21") (pinfunction "B_RESET#_AK21") (pintype "bidirectional"))
      (node (ref "R49") (pin "2") (pinfunction "-_2") (pintype "passive"))
      (node (ref "U1") (pin "T2") (pinfunction "RESET#_T2") (pintype "input"))
      (node (ref "U2") (pin "T2") (pinfunction "RESET#_T2") (pintype "input"))
    )
    (net (code "72") (name "/FPGA_DDR_WE#") (class "Default")
      (node (ref "D2") (pin "AJ6") (pinfunction "B_WE#_AJ6") (pintype "bidirectional"))
      (node (ref "R42") (pin "5") (pintype "passive"))
      (node (ref "U1") (pin "L3") (pinfunction "WE#_L3") (pintype "input"))
      (node (ref "U2") (pin "L3") (pinfunction "WE#_L3") (pintype "input"))
    )
    (net (code "74") (name "/LVDS0_CKI_P") (class "Default")
      (node (ref "D2") (pin "W15") (pinfunction "CLK1p_W15") (pintype "bidirectional"))
    )
    (net (code "76") (name "/LVDS0_RX0_P") (class "Default")
      (node (ref "D2") (pin "AF11") (pinfunction "DIFFIO_RX_B18p_AF11") (pintype "bidirectional"))
    )
    (net (code "77") (name "/LVDS0_RX1_N") (class "Default")
      (node (ref "D2") (pin "AB13") (pinfunction "DIFFIO_RX_B19n_AB13") (pintype "bidirectional"))
    )
    (net (code "78") (name "/LVDS0_RX1_P") (class "Default")
      (node (ref "D2") (pin "AA13") (pinfunction "DIFFIO_RX_B19p_AA13") (pintype "bidirectional"))
    )
    (net (code "79") (name "/LVDS0_RX2_N") (class "Default")
      (node (ref "D2") (pin "AF13") (pinfunction "DIFFIO_RX_B22n_AF13") (pintype "bidirectional"))
    )
    (net (code "80") (name "/LVDS0_RX2_P") (class "Default")
      (node (ref "D2") (pin "AE13") (pinfunction "DIFFIO_RX_B22p_AE13") (pintype "bidirectional"))
    )
    (net (code "82") (name "/LVDS0_RX3_N") (class "Default")
      (node (ref "D2") (pin "AE14") (pinfunction "DIFFIO_RX_B23n_AE14") (pintype "bidirectional"))
    )
    (net (code "83") (name "/LVDS0_RX3_P") (class "Default")
      (node (ref "D2") (pin "AD14") (pinfunction "DIFFIO_RX_B23p_AD14") (pintype "bidirectional"))
    )
    (net (code "84") (name "/OSC_50_1") (class "Default")
      (node (ref "C9") (pin "1") (pinfunction "+_1") (pintype "passive"))
    )
    (net (code "85") (name "/OSC_50_2") (class "Default")
      (node (ref "C10") (pin "1") (pinfunction "+_1") (pintype "passive"))
    )
    (net (code "86") (name "/OSC_50_B3B") (class "Default")
      (node (ref "C9") (pin "2") (pinfunction "-_2") (pintype "passive"))
      (node (ref "D2") (pin "AF14") (pinfunction "CLK0p_AF14") (pintype "bidirectional"))
      (node (ref "R43") (pin "1") (pinfunction "+_1") (pintype "passive"))
      (node (ref "R44") (pin "1") (pinfunction "+_1") (pintype "passive"))
    )
    (net (code "88") (name "/OSC_50_B4B") (class "Default")
      (node (ref "C10") (pin "2") (pinfunction "-_2") (pintype "passive"))
      (node (ref "D2") (pin "AA16") (pinfunction "CLK2p_AA16") (pintype "bidirectional"))
      (node (ref "R45") (pin "1") (pinfunction "+_1") (pintype "passive"))
      (node (ref "R46") (pin "1") (pinfunction "+_1") (pintype "passive"))
    )
    (net (code "89") (name "DDR3_VREF_FPGA") (class "Default")
      (node (ref "C15") (pin "1") (pinfunction "+_1") (pintype "passive"))
      (node (ref "D5") (pin "6") (pinfunction "REFOUT_6") (pintype "power_in"))
      (node (ref "U1") (pin "H1") (pinfunction "VREFDQ_H1") (pintype "input"))
      (node (ref "U1") (pin "M8") (pinfunction "VREFCA_M8") (pintype "input"))
      (node (ref "U2") (pin "H1") (pinfunction "VREFDQ_H1") (pintype "input"))
      (node (ref "U2") (pin "M8") (pinfunction "VREFCA_M8") (pintype "input"))
    )
    (net (code "90") (name "DDR3_VTT_FPGA") (class "Default")
      (node (ref "C17") (pin "1") (pinfunction "+_1") (pintype "passive"))
      (node (ref "C18") (pin "1") (pinfunction "+_1") (pintype "passive"))
      (node (ref "C6") (pin "5") (pintype "passive"))
      (node (ref "C6") (pin "6") (pintype "passive"))
      (node (ref "C6") (pin "7") (pintype "passive"))
      (node (ref "C6") (pin "8") (pintype "passive"))
      (node (ref "C7") (pin "5") (pintype "passive"))
      (node (ref "C7") (pin "6") (pintype "passive"))
      (node (ref "C7") (pin "7") (pintype "passive"))
      (node (ref "C7") (pin "8") (pintype "passive"))
      (node (ref "C8") (pin "5") (pintype "passive"))
      (node (ref "C8") (pin "6") (pintype "passive"))
      (node (ref "C8") (pin "7") (pintype "passive"))
      (node (ref "C8") (pin "8") (pintype "passive"))
      (node (ref "D5") (pin "3") (pinfunction "VO_3") (pintype "power_in"))
      (node (ref "D5") (pin "5") (pinfunction "VOSNS_5") (pintype "input"))
      (node (ref "R40") (pin "10") (pintype "passive"))
      (node (ref "R40") (pin "11") (pintype "passive"))
      (node (ref "R40") (pin "12") (pintype "passive"))
      (node (ref "R40") (pin "13") (pintype "passive"))
      (node (ref "R40") (pin "14") (pintype "passive"))
      (node (ref "R40") (pin "15") (pintype "passive"))
      (node (ref "R40") (pin "16") (pintype "passive"))
      (node (ref "R40") (pin "9") (pintype "passive"))
      (node (ref "R41") (pin "10") (pintype "passive"))
      (node (ref "R41") (pin "11") (pintype "passive"))
      (node (ref "R41") (pin "12") (pintype "passive"))
      (node (ref "R41") (pin "13") (pintype "passive"))
      (node (ref "R41") (pin "14") (pintype "passive"))
      (node (ref "R41") (pin "15") (pintype "passive"))
      (node (ref "R41") (pin "16") (pintype "passive"))
      (node (ref "R41") (pin "9") (pintype "passive"))
      (node (ref "R42") (pin "10") (pintype "passive"))
      (node (ref "R42") (pin "11") (pintype "passive"))
      (node (ref "R42") (pin "12") (pintype "passive"))
      (node (ref "R42") (pin "13") (pintype "passive"))
      (node (ref "R42") (pin "14") (pintype "passive"))
      (node (ref "R42") (pin "15") (pintype "passive"))
      (node (ref "R42") (pin "16") (pintype "passive"))
      (node (ref "R42") (pin "9") (pintype "passive"))
    )
    (net (code "91") (name "GND") (class "Default")
      (node (ref "C15") (pin "2") (pinfunction "-_2") (pintype "passive"))
      (node (ref "C16") (pin "2") (pinfunction "-_2") (pintype "passive"))
      (node (ref "C17") (pin "2") (pinfunction "-_2") (pintype "passive"))
      (node (ref "C18") (pin "2") (pinfunction "-_2") (pintype "passive"))
      (node (ref "C19") (pin "2") (pinfunction "-_2") (pintype "passive"))
      (node (ref "C20") (pin "2") (pinfunction "-_2") (pintype "passive"))
      (node (ref "C6") (pin "1") (pintype "passive"))
      (node (ref "C6") (pin "2") (pintype "passive"))
      (node (ref "C6") (pin "3") (pintype "passive"))
      (node (ref "C6") (pin "4") (pintype "passive"))
      (node (ref "C7") (pin "1") (pintype "passive"))
      (node (ref "C7") (pin "2") (pintype "passive"))
      (node (ref "C7") (pin "3") (pintype "passive"))
      (node (ref "C7") (pin "4") (pintype "passive"))
      (node (ref "C8") (pin "1") (pintype "passive"))
      (node (ref "C8") (pin "2") (pintype "passive"))
      (node (ref "C8") (pin "3") (pintype "passive"))
      (node (ref "C8") (pin "4") (pintype "passive"))
      (node (ref "D2") (pin "AF15") (pinfunction "CLK0n_AF15") (pintype "bidirectional"))
      (node (ref "D2") (pin "AJ10") (pinfunction "GND_AJ10") (pintype "bidirectional"))
      (node (ref "D2") (pin "AJ22") (pinfunction "GND_AJ22") (pintype "bidirectional"))
      (node (ref "D2") (pin "AJ7") (pinfunction "GND_AJ7") (pintype "bidirectional"))
      (node (ref "D5") (pin "11") (pinfunction "EP_11") (pintype "power_in"))
      (node (ref "D5") (pin "4") (pinfunction "PGND_4") (pintype "power_in"))
      (node (ref "D5") (pin "8") (pinfunction "GND_8") (pintype "power_in"))
      (node (ref "R190") (pin "1") (pinfunction "+_1") (pintype "passive"))
      (node (ref "R44") (pin "2") (pinfunction "-_2") (pintype "passive"))
      (node (ref "R46") (pin "2") (pinfunction "-_2") (pintype "passive"))
      (node (ref "R47") (pin "2") (pinfunction "-_2") (pintype "passive"))
      (node (ref "R48") (pin "2") (pinfunction "-_2") (pintype "passive"))
      (node (ref "R57") (pin "2") (pinfunction "-_2") (pintype "passive"))
      (node (ref "R59") (pin "1") (pinfunction "+_1") (pintype "passive"))
      (node (ref "U1") (pin "A9") (pinfunction "VSS_A9") (pintype "power_in"))
      (node (ref "U1") (pin "B1") (pinfunction "VSSQ_B1") (pintype "power_in"))
      (node (ref "U1") (pin "B3") (pinfunction "VSS_B3") (pintype "power_in"))
      (node (ref "U1") (pin "B9") (pinfunction "VSSQ_B9") (pintype "power_in"))
      (node (ref "U1") (pin "D1") (pinfunction "VSSQ_D1") (pintype "power_in"))
      (node (ref "U1") (pin "D8") (pinfunction "VSSQ_D8") (pintype "power_in"))
      (node (ref "U1") (pin "E1") (pinfunction "VSS_E1") (pintype "power_in"))
      (node (ref "U1") (pin "E2") (pinfunction "VSSQ_E2") (pintype "power_in"))
      (node (ref "U1") (pin "E8") (pinfunction "VSSQ_E8") (pintype "power_in"))
      (node (ref "U1") (pin "F9") (pinfunction "VSSQ_F9") (pintype "power_in"))
      (node (ref "U1") (pin "G1") (pinfunction "VSSQ_G1") (pintype "power_in"))
      (node (ref "U1") (pin "G8") (pinfunction "VSS_G8") (pintype "power_in"))
      (node (ref "U1") (pin "G9") (pinfunction "VSSQ_G9") (pintype "power_in"))
      (node (ref "U1") (pin "J2") (pinfunction "VSS_J2") (pintype "power_in"))
      (node (ref "U1") (pin "J8") (pinfunction "VSS_J8") (pintype "power_in"))
      (node (ref "U1") (pin "M1") (pinfunction "VSS_M1") (pintype "power_in"))
      (node (ref "U1") (pin "M9") (pinfunction "VSS_M9") (pintype "power_in"))
      (node (ref "U1") (pin "P1") (pinfunction "VSS_P1") (pintype "power_in"))
      (node (ref "U1") (pin "P9") (pinfunction "VSS_P9") (pintype "power_in"))
      (node (ref "U1") (pin "T1") (pinfunction "VSS_T1") (pintype "power_in"))
      (node (ref "U1") (pin "T9") (pinfunction "VSS_T9") (pintype "power_in"))
      (node (ref "U2") (pin "A9") (pinfunction "VSS_A9") (pintype "power_in"))
      (node (ref "U2") (pin "B1") (pinfunction "VSSQ_B1") (pintype "power_in"))
      (node (ref "U2") (pin "B3") (pinfunction "VSS_B3") (pintype "power_in"))
      (node (ref "U2") (pin "B9") (pinfunction "VSSQ_B9") (pintype "power_in"))
      (node (ref "U2") (pin "D1") (pinfunction "VSSQ_D1") (pintype "power_in"))
      (node (ref "U2") (pin "D8") (pinfunction "VSSQ_D8") (pintype "power_in"))
      (node (ref "U2") (pin "E1") (pinfunction "VSS_E1") (pintype "power_in"))
      (node (ref "U2") (pin "E2") (pinfunction "VSSQ_E2") (pintype "power_in"))
      (node (ref "U2") (pin "E8") (pinfunction "VSSQ_E8") (pintype "power_in"))
      (node (ref "U2") (pin "F9") (pinfunction "VSSQ_F9") (pintype "power_in"))
      (node (ref "U2") (pin "G1") (pinfunction "VSSQ_G1") (pintype "power_in"))
      (node (ref "U2") (pin "G8") (pinfunction "VSS_G8") (pintype "power_in"))
      (node (ref "U2") (pin "G9") (pinfunction "VSSQ_G9") (pintype "power_in"))
      (node (ref "U2") (pin "J2") (pinfunction "VSS_J2") (pintype "power_in"))
      (node (ref "U2") (pin "J8") (pinfunction "VSS_J8") (pintype "power_in"))
      (node (ref "U2") (pin "M1") (pinfunction "VSS_M1") (pintype "power_in"))
      (node (ref "U2") (pin "M9") (pinfunction "VSS_M9") (pintype "power_in"))
      (node (ref "U2") (pin "P1") (pinfunction "VSS_P1") (pintype "power_in"))
      (node (ref "U2") (pin "P9") (pinfunction "VSS_P9") (pintype "power_in"))
      (node (ref "U2") (pin "T1") (pinfunction "VSS_T1") (pintype "power_in"))
      (node (ref "U2") (pin "T9") (pinfunction "VSS_T9") (pintype "power_in"))
    )
    (net (code "92") (name "Net-(C20-+)") (class "Default")
      (node (ref "C20") (pin "1") (pinfunction "+_1") (pintype "passive"))
      (node (ref "D5") (pin "1") (pinfunction "REFIN_1") (pintype "input"))
      (node (ref "R58") (pin "2") (pinfunction "-_2") (pintype "passive"))
      (node (ref "R59") (pin "2") (pinfunction "-_2") (pintype "passive"))
    )
    (net (code "93") (name "Net-(D2C-RZQ_0)") (class "Default")
      (node (ref "D2") (pin "AG17") (pinfunction "RZQ_0_AG17") (pintype "bidirectional"))
      (node (ref "R57") (pin "1") (pinfunction "+_1") (pintype "passive"))
    )
    (net (code "94") (name "Net-(D5-EN)") (class "Default")
      (node (ref "D5") (pin "7") (pinfunction "EN_7") (pintype "input"))
      (node (ref "R56") (pin "2") (pinfunction "-_2") (pintype "passive"))
    )
    (net (code "95") (name "Net-(D5-PGOOD)") (class "Default")
      (node (ref "D5") (pin "9") (pinfunction "PGOOD_9") (pintype "open_collector"))
      (node (ref "R55") (pin "2") (pinfunction "-_2") (pintype "passive"))
    )
    (net (code "96") (name "Net-(R47-+)") (class "Default")
      (node (ref "R47") (pin "1") (pinfunction "+_1") (pintype "passive"))
      (node (ref "U1") (pin "L8") (pinfunction "ZQ_L8") (pintype "input"))
    )
    (net (code "97") (name "Net-(R48-+)") (class "Default")
      (node (ref "R48") (pin "1") (pinfunction "+_1") (pintype "passive"))
      (node (ref "U2") (pin "L8") (pinfunction "ZQ_L8") (pintype "input"))
    )
    (net (code "98") (name "VCC1P5_DDR3") (class "Default")
      (node (ref "C19") (pin "1") (pinfunction "+_1") (pintype "passive"))
      (node (ref "D5") (pin "2") (pinfunction "VLDOIN_2") (pintype "power_in"))
      (node (ref "R49") (pin "1") (pinfunction "+_1") (pintype "passive"))
      (node (ref "R58") (pin "1") (pinfunction "+_1") (pintype "passive"))
      (node (ref "U1") (pin "A1") (pinfunction "VDDQ_A1") (pintype "power_in"))
      (node (ref "U1") (pin "A8") (pinfunction "VDDQ_A8") (pintype "power_in"))
      (node (ref "U1") (pin "B2") (pinfunction "VDD_B2") (pintype "power_in"))
      (node (ref "U1") (pin "C1") (pinfunction "VDDQ_C1") (pintype "power_in"))
      (node (ref "U1") (pin "C9") (pinfunction "VDDQ_C9") (pintype "power_in"))
      (node (ref "U1") (pin "D2") (pinfunction "VDDQ_D2") (pintype "power_in"))
      (node (ref "U1") (pin "D9") (pinfunction "VDD_D9") (pintype "power_in"))
      (node (ref "U1") (pin "E9") (pinfunction "VDDQ_E9") (pintype "power_in"))
      (node (ref "U1") (pin "F1") (pinfunction "VDDQ_F1") (pintype "power_in"))
      (node (ref "U1") (pin "G7") (pinfunction "VDD_G7") (pintype "power_in"))
      (node (ref "U1") (pin "H2") (pinfunction "VDDQ_H2") (pintype "power_in"))
      (node (ref "U1") (pin "H9") (pinfunction "VDDQ_H9") (pintype "power_in"))
      (node (ref "U1") (pin "K2") (pinfunction "VDD_K2") (pintype "power_in"))
      (node (ref "U1") (pin "K8") (pinfunction "VDD_K8") (pintype "power_in"))
      (node (ref "U1") (pin "N1") (pinfunction "VDD_N1") (pintype "power_in"))
      (node (ref "U1") (pin "N9") (pinfunction "VDD_N9") (pintype "power_in"))
      (node (ref "U1") (pin "R1") (pinfunction "VDD_R1") (pintype "power_in"))
      (node (ref "U1") (pin "R9") (pinfunction "VDD_R9") (pintype "power_in"))
      (node (ref "U2") (pin "A1") (pinfunction "VDDQ_A1") (pintype "power_in"))
      (node (ref "U2") (pin "A8") (pinfunction "VDDQ_A8") (pintype "power_in"))
      (node (ref "U2") (pin "B2") (pinfunction "VDD_B2") (pintype "power_in"))
      (node (ref "U2") (pin "C1") (pinfunction "VDDQ_C1") (pintype "power_in"))
      (node (ref "U2") (pin "C9") (pinfunction "VDDQ_C9") (pintype "power_in"))
      (node (ref "U2") (pin "D2") (pinfunction "VDDQ_D2") (pintype "power_in"))
      (node (ref "U2") (pin "D9") (pinfunction "VDD_D9") (pintype "power_in"))
      (node (ref "U2") (pin "E9") (pinfunction "VDDQ_E9") (pintype "power_in"))
      (node (ref "U2") (pin "F1") (pinfunction "VDDQ_F1") (pintype "power_in"))
      (node (ref "U2") (pin "G7") (pinfunction "VDD_G7") (pintype "power_in"))
      (node (ref "U2") (pin "H2") (pinfunction "VDDQ_H2") (pintype "power_in"))
      (node (ref "U2") (pin "H9") (pinfunction "VDDQ_H9") (pintype "power_in"))
      (node (ref "U2") (pin "K2") (pinfunction "VDD_K2") (pintype "power_in"))
      (node (ref "U2") (pin "K8") (pinfunction "VDD_K8") (pintype "power_in"))
      (node (ref "U2") (pin "N1") (pinfunction "VDD_N1") (pintype "power_in"))
      (node (ref "U2") (pin "N9") (pinfunction "VDD_N9") (pintype "power_in"))
      (node (ref "U2") (pin "R1") (pinfunction "VDD_R1") (pintype "power_in"))
      (node (ref "U2") (pin "R9") (pinfunction "VDD_R9") (pintype "power_in"))
    )
    (net (code "99") (name "VCC2P5") (class "Default")
      (node (ref "R43") (pin "2") (pinfunction "-_2") (pintype "passive"))
      (node (ref "R45") (pin "2") (pinfunction "-_2") (pintype "passive"))
    )
    (net (code "100") (name "VCC3P3") (class "Default")
      (node (ref "C16") (pin "1") (pinfunction "+_1") (pintype "passive"))
      (node (ref "D5") (pin "10") (pinfunction "VIN_10") (pintype "power_in"))
      (node (ref "R55") (pin "1") (pinfunction "+_1") (pintype "passive"))
      (node (ref "R56") (pin "1") (pinfunction "+_1") (pintype "passive"))
    )
    (net (code "101") (name "unconnected-(D2B-CLK1n-PadY16)") (class "Default")
      (node (ref "D2") (pin "Y16") (pinfunction "CLK1n_Y16") (pintype "bidirectional"))
    )
    (net (code "102") (name "unconnected-(D2B-DIFFIO_RX_B18n-PadAG11)") (class "Default")
      (node (ref "D2") (pin "AG11") (pinfunction "DIFFIO_RX_B18n_AG11") (pintype "bidirectional"))
    )
    (net (code "103") (name "unconnected-(D2B-DIFFIO_TX_B17n-PadAH9)") (class "Default")
      (node (ref "D2") (pin "AH9") (pinfunction "DIFFIO_TX_B17n_AH9") (pintype "bidirectional+no_connect"))
    )
    (net (code "104") (name "unconnected-(D2B-DIFFIO_TX_B17p-PadAG10)") (class "Default")
      (node (ref "D2") (pin "AG10") (pinfunction "DIFFIO_TX_B17p_AG10") (pintype "bidirectional+no_connect"))
    )
    (net (code "105") (name "unconnected-(D2B-DIFFIO_TX_B20n-PadAK3)") (class "Default")
      (node (ref "D2") (pin "AK3") (pinfunction "DIFFIO_TX_B20n_AK3") (pintype "bidirectional+no_connect"))
    )
    (net (code "106") (name "unconnected-(D2B-DIFFIO_TX_B20p-PadAK2)") (class "Default")
      (node (ref "D2") (pin "AK2") (pinfunction "DIFFIO_TX_B20p_AK2") (pintype "bidirectional+no_connect"))
    )
    (net (code "107") (name "unconnected-(D2B-DIFFIO_TX_B21n-PadAK4)") (class "Default")
      (node (ref "D2") (pin "AK4") (pinfunction "DIFFIO_TX_B21n_AK4") (pintype "bidirectional+no_connect"))
    )
    (net (code "108") (name "unconnected-(D2B-DIFFIO_TX_B21p-PadAJ4)") (class "Default")
      (node (ref "D2") (pin "AJ4") (pinfunction "DIFFIO_TX_B21p_AJ4") (pintype "bidirectional+no_connect"))
    )
    (net (code "109") (name "unconnected-(D2B-DIFFIO_TX_B24n-PadAK6)") (class "Default")
      (node (ref "D2") (pin "AK6") (pinfunction "DIFFIO_TX_B24n_AK6") (pintype "bidirectional+no_connect"))
    )
    (net (code "110") (name "unconnected-(D2B-DIFFIO_TX_B24p-PadAJ5)") (class "Default")
      (node (ref "D2") (pin "AJ5") (pinfunction "DIFFIO_TX_B24p_AJ5") (pintype "bidirectional+no_connect"))
    )
    (net (code "111") (name "unconnected-(D2B-IO-PadAC14)") (class "Default")
      (node (ref "D2") (pin "AC14") (pinfunction "IO_AC14") (pintype "bidirectional+no_connect"))
    )
    (net (code "112") (name "unconnected-(D2B-IO-PadAG13)") (class "Default")
      (node (ref "D2") (pin "AG13") (pinfunction "IO_AG13") (pintype "bidirectional+no_connect"))
    )
    (net (code "113") (name "unconnected-(D2C-CLK2n-PadAB17)") (class "Default")
      (node (ref "D2") (pin "AB17") (pinfunction "CLK2n_AB17") (pintype "bidirectional"))
    )
    (net (code "114") (name "unconnected-(D2C-CLK3n-PadAD17)") (class "Default")
      (node (ref "D2") (pin "AD17") (pinfunction "CLK3n_AD17") (pintype "bidirectional"))
    )
    (net (code "115") (name "unconnected-(D2C-CLK3p-PadAC18)") (class "Default")
      (node (ref "D2") (pin "AC18") (pinfunction "CLK3p_AC18") (pintype "bidirectional"))
    )
    (net (code "116") (name "unconnected-(D2C-DIFFIO_RX_B74n-PadAD21)") (class "Default")
      (node (ref "D2") (pin "AD21") (pinfunction "DIFFIO_RX_B74n_AD21") (pintype "bidirectional+no_connect"))
    )
    (net (code "117") (name "unconnected-(D2C-DIFFIO_RX_B74p-PadAD20)") (class "Default")
      (node (ref "D2") (pin "AD20") (pinfunction "DIFFIO_RX_B74p_AD20") (pintype "bidirectional+no_connect"))
    )
    (net (code "118") (name "unconnected-(D2C-DIFFIO_RX_B75n-PadAA20)") (class "Default")
      (node (ref "D2") (pin "AA20") (pinfunction "DIFFIO_RX_B75n_AA20") (pintype "bidirectional+no_connect"))
    )
    (net (code "119") (name "unconnected-(D2C-DIFFIO_RX_B75p-PadY19)") (class "Default")
      (node (ref "D2") (pin "Y19") (pinfunction "DIFFIO_RX_B75p_Y19") (pintype "bidirectional+no_connect"))
    )
    (net (code "120") (name "unconnected-(D2C-DIFFIO_RX_B78n-PadAC23)") (class "Default")
      (node (ref "D2") (pin "AC23") (pinfunction "DIFFIO_RX_B78n_AC23") (pintype "bidirectional+no_connect"))
    )
    (net (code "121") (name "unconnected-(D2C-DIFFIO_RX_B78p-PadAC22)") (class "Default")
      (node (ref "D2") (pin "AC22") (pinfunction "DIFFIO_RX_B78p_AC22") (pintype "bidirectional+no_connect"))
    )
    (net (code "122") (name "unconnected-(D2C-DIFFIO_TX_B80n-PadAE24)") (class "Default")
      (node (ref "D2") (pin "AE24") (pinfunction "DIFFIO_TX_B80n_AE24") (pintype "bidirectional+no_connect"))
    )
    (net (code "123") (name "unconnected-(D2C-DIFFIO_TX_B80p-PadAD24)") (class "Default")
      (node (ref "D2") (pin "AD24") (pinfunction "DIFFIO_TX_B80p_AD24") (pintype "bidirectional+no_connect"))
    )
    (net (code "124") (name "unconnected-(D2C-GND-PadAA19)") (class "Default")
      (node (ref "D2") (pin "AA19") (pinfunction "GND_AA19") (pintype "bidirectional"))
    )
    (net (code "125") (name "unconnected-(D2C-GND-PadAA21)") (class "Default")
      (node (ref "D2") (pin "AA21") (pinfunction "GND_AA21") (pintype "bidirectional"))
    )
    (net (code "126") (name "unconnected-(D2C-GND-PadAB21)") (class "Default")
      (node (ref "D2") (pin "AB21") (pinfunction "GND_AB21") (pintype "bidirectional"))
    )
    (net (code "127") (name "unconnected-(D2C-GND-PadAF26)") (class "Default")
      (node (ref "D2") (pin "AF26") (pinfunction "GND_AF26") (pintype "bidirectional"))
    )
    (net (code "128") (name "unconnected-(D2C-GND-PadAG26)") (class "Default")
      (node (ref "D2") (pin "AG26") (pinfunction "GND_AG26") (pintype "bidirectional"))
    )
    (net (code "129") (name "unconnected-(D2C-GND-PadAH19)") (class "Default")
      (node (ref "D2") (pin "AH19") (pinfunction "GND_AH19") (pintype "bidirectional"))
    )
    (net (code "130") (name "unconnected-(D2C-GND-PadAH22)") (class "Default")
      (node (ref "D2") (pin "AH22") (pinfunction "GND_AH22") (pintype "bidirectional"))
    )
    (net (code "131") (name "unconnected-(D2C-GND-PadAH25)") (class "Default")
      (node (ref "D2") (pin "AH25") (pinfunction "GND_AH25") (pintype "bidirectional"))
    )
    (net (code "132") (name "unconnected-(D2C-GND-PadAJ25)") (class "Default")
      (node (ref "D2") (pin "AJ25") (pinfunction "GND_AJ25") (pintype "bidirectional"))
    )
    (net (code "133") (name "unconnected-(D2C-GND-PadAJ26)") (class "Default")
      (node (ref "D2") (pin "AJ26") (pinfunction "GND_AJ26") (pintype "bidirectional"))
    )
    (net (code "134") (name "unconnected-(D2C-GND-PadAK29)") (class "Default")
      (node (ref "D2") (pin "AK29") (pinfunction "GND_AK29") (pintype "bidirectional"))
    )
    (net (code "135") (name "unconnected-(D2C-GND-PadV18)") (class "Default")
      (node (ref "D2") (pin "V18") (pinfunction "GND_V18") (pintype "bidirectional"))
    )
    (net (code "136") (name "unconnected-(D2C-GND-PadW19)") (class "Default")
      (node (ref "D2") (pin "W19") (pinfunction "GND_W19") (pintype "bidirectional"))
    )
    (net (code "137") (name "unconnected-(D2C-GND-PadY18)") (class "Default")
      (node (ref "D2") (pin "Y18") (pinfunction "GND_Y18") (pintype "bidirectional"))
    )
    (net (code "138") (name "unconnected-(D2C-IO-PadAF25)") (class "Default")
      (node (ref "D2") (pin "AF25") (pinfunction "IO_AF25") (pintype "bidirectional+no_connect"))
    )
    (net (code "139") (name "unconnected-(D2C-IO-PadAH27)") (class "Default")
      (node (ref "D2") (pin "AH27") (pinfunction "IO_AH27") (pintype "bidirectional+no_connect"))
    )
    (net (code "140") (name "unconnected-(D2C-IO-PadAJ19)") (class "Default")
      (node (ref "D2") (pin "AJ19") (pinfunction "IO_AJ19") (pintype "bidirectional+no_connect"))
    )
    (net (code "141") (name "unconnected-(D2C-IO-PadAK16)") (class "Default")
      (node (ref "D2") (pin "AK16") (pinfunction "IO_AK16") (pintype "bidirectional+no_connect"))
    )
    (net (code "142") (name "unconnected-(D2C-IO-PadAK28)") (class "Default")
      (node (ref "D2") (pin "AK28") (pinfunction "IO_AK28") (pintype "bidirectional+no_connect"))
    )
    (net (code "143") (name "unconnected-(U1C-NC-PadJ1)") (class "Default")
      (node (ref "U1") (pin "J1") (pinfunction "NC_J1") (pintype "passive"))
    )
    (net (code "144") (name "unconnected-(U1C-NC-PadJ9)") (class "Default")
      (node (ref "U1") (pin "J9") (pinfunction "NC_J9") (pintype "passive"))
    )
    (net (code "145") (name "unconnected-(U1C-NC-PadL1)") (class "Default")
      (node (ref "U1") (pin "L1") (pinfunction "NC_L1") (pintype "passive"))
    )
    (net (code "146") (name "unconnected-(U1C-NC-PadL9)") (class "Default")
      (node (ref "U1") (pin "L9") (pinfunction "NC_L9") (pintype "passive"))
    )
    (net (code "147") (name "unconnected-(U1C-NC-PadM7)") (class "Default")
      (node (ref "U1") (pin "M7") (pinfunction "NC_M7") (pintype "passive"))
    )
    (net (code "148") (name "unconnected-(U2C-NC-PadJ1)") (class "Default")
      (node (ref "U2") (pin "J1") (pinfunction "NC_J1") (pintype "passive"))
    )
    (net (code "149") (name "unconnected-(U2C-NC-PadJ9)") (class "Default")
      (node (ref "U2") (pin "J9") (pinfunction "NC_J9") (pintype "passive"))
    )
    (net (code "150") (name "unconnected-(U2C-NC-PadL1)") (class "Default")
      (node (ref "U2") (pin "L1") (pinfunction "NC_L1") (pintype "passive"))
    )
    (net (code "151") (name "unconnected-(U2C-NC-PadL9)") (class "Default")
      (node (ref "U2") (pin "L9") (pinfunction "NC_L9") (pintype "passive"))
    )
    (net (code "152") (name "unconnected-(U2C-NC-PadM7)") (class "Default")
      (node (ref "U2") (pin "M7") (pinfunction "NC_M7") (pintype "passive"))
    )
  )
)
